# zero_board.net
KiCad netlist of a schematic drawn in EAGLE
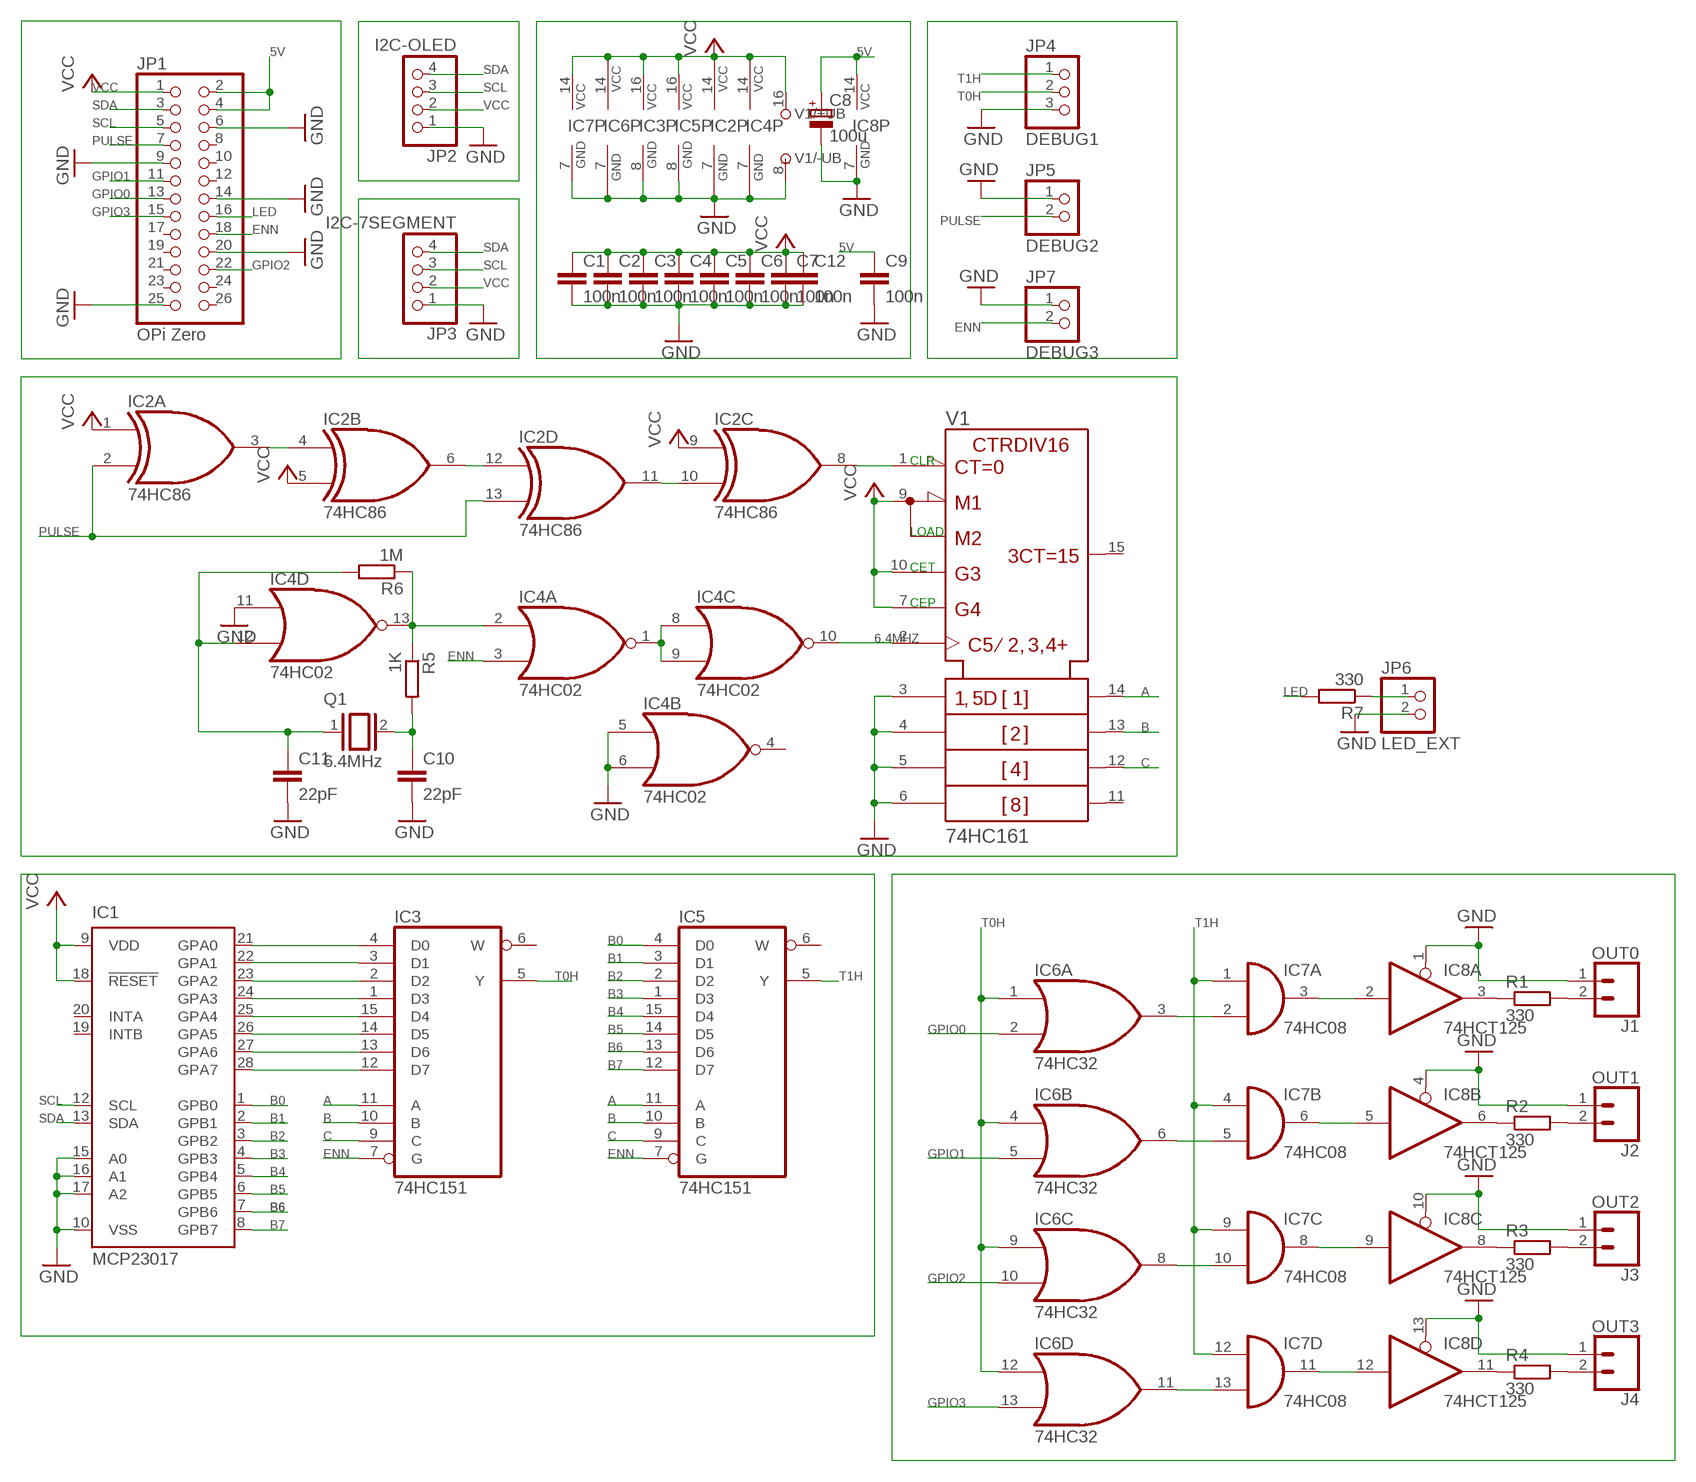
[diagram p0: schematic, sheet 1]

(export (version "E")
  (design (tool "Eeschema 10.0.6"))
  (components
    (comp (ref "C1")
      (value "100n")
      (footprint "eagle-import:C050-024X044")
      (libsource (lib "eagle-import") (part "C-EU050-024X044"))
    )
    (comp (ref "C2")
      (value "100n")
      (footprint "eagle-import:C050-024X044")
      (libsource (lib "eagle-import") (part "C-EU050-024X044"))
    )
    (comp (ref "C3")
      (value "100n")
      (footprint "eagle-import:C050-024X044")
      (libsource (lib "eagle-import") (part "C-EU050-024X044"))
    )
    (comp (ref "C4")
      (value "100n")
      (footprint "eagle-import:C050-024X044")
      (libsource (lib "eagle-import") (part "C-EU050-024X044"))
    )
    (comp (ref "C5")
      (value "100n")
      (footprint "eagle-import:C050-024X044")
      (libsource (lib "eagle-import") (part "C-EU050-024X044"))
    )
    (comp (ref "C6")
      (value "100n")
      (footprint "eagle-import:C050-024X044")
      (libsource (lib "eagle-import") (part "C-EU050-024X044"))
    )
    (comp (ref "C7")
      (value "100n")
      (footprint "eagle-import:C050-024X044")
      (libsource (lib "eagle-import") (part "C-EU050-024X044"))
    )
    (comp (ref "C8")
      (value "100u")
      (footprint "eagle-import:E2,5-6")
      (libsource (lib "eagle-import") (part "CPOL-EUE2.5-6"))
    )
    (comp (ref "C9")
      (value "100n")
      (footprint "eagle-import:C050-024X044")
      (libsource (lib "eagle-import") (part "C-EU050-024X044"))
    )
    (comp (ref "C10")
      (value "22pF")
      (footprint "eagle-import:C050-024X044")
      (libsource (lib "eagle-import") (part "C-EU050-024X044"))
    )
    (comp (ref "C11")
      (value "22pF")
      (footprint "eagle-import:C050-024X044")
      (libsource (lib "eagle-import") (part "C-EU050-024X044"))
    )
    (comp (ref "C12")
      (value "100n")
      (footprint "eagle-import:C050-024X044")
      (libsource (lib "eagle-import") (part "C-EU050-024X044"))
    )
    (comp (ref "IC1")
      (value "MCP23017")
      (footprint "eagle-import:DIL28-3")
      (fields (field (name "MF") "MICROCHIP") (field (name "MPN") "MCP23017-E/SP"))
      (libsource (lib "eagle-import") (part "MCP23017SP"))
    )
    (comp (ref "IC2")
      (value "74HC86")
      (footprint "eagle-import:DIL14")
      (libsource (lib "eagle-import") (part "7486NLS"))
    )
    (comp (ref "IC3")
      (value "74HC151")
      (footprint "eagle-import:DIL16")
      (libsource (lib "eagle-import") (part "74151NHC"))
    )
    (comp (ref "IC4")
      (value "74HC02")
      (footprint "eagle-import:DIL14")
      (libsource (lib "eagle-import") (part "7402N"))
    )
    (comp (ref "IC5")
      (value "74HC151")
      (footprint "eagle-import:DIL16")
      (libsource (lib "eagle-import") (part "74151NHC"))
    )
    (comp (ref "IC6")
      (value "74HC32")
      (footprint "eagle-import:DIL14")
      (libsource (lib "eagle-import") (part "7432NLS"))
    )
    (comp (ref "IC7")
      (value "74HC08")
      (footprint "eagle-import:DIL14")
      (libsource (lib "eagle-import") (part "7408NAS"))
    )
    (comp (ref "IC8")
      (value "74HCT125")
      (footprint "eagle-import:DIL14")
      (libsource (lib "eagle-import") (part "74125NHC"))
    )
    (comp (ref "J1")
      (value "OUT0")
      (footprint "eagle-import:SCREWTERMINAL-3.5MM-2")
      (libsource (lib "eagle-import") (part "CONN_023.5MM"))
    )
    (comp (ref "J2")
      (value "OUT1")
      (footprint "eagle-import:SCREWTERMINAL-3.5MM-2")
      (libsource (lib "eagle-import") (part "CONN_023.5MM"))
    )
    (comp (ref "J3")
      (value "OUT2")
      (footprint "eagle-import:SCREWTERMINAL-3.5MM-2")
      (libsource (lib "eagle-import") (part "CONN_023.5MM"))
    )
    (comp (ref "J4")
      (value "OUT3")
      (footprint "eagle-import:SCREWTERMINAL-3.5MM-2")
      (libsource (lib "eagle-import") (part "CONN_023.5MM"))
    )
    (comp (ref "JP1")
      (value "OPi Zero")
      (footprint "eagle-import:2X13")
      (libsource (lib "eagle-import") (part "PINHD-2X13"))
    )
    (comp (ref "JP2")
      (value "I2C-OLED")
      (footprint "eagle-import:1X04")
      (libsource (lib "eagle-import") (part "PINHD-1X4"))
    )
    (comp (ref "JP3")
      (value "I2C-7SEGMENT")
      (footprint "eagle-import:1X04")
      (libsource (lib "eagle-import") (part "PINHD-1X4"))
    )
    (comp (ref "JP4")
      (value "DEBUG1")
      (footprint "eagle-import:1X03_90")
      (libsource (lib "eagle-import") (part "PINHD-1X3/90"))
    )
    (comp (ref "JP5")
      (value "DEBUG2")
      (footprint "eagle-import:1X02_90")
      (libsource (lib "eagle-import") (part "PINHD-1X2/90"))
    )
    (comp (ref "JP6")
      (value "LED_EXT")
      (footprint "eagle-import:1X02_90")
      (libsource (lib "eagle-import") (part "PINHD-1X2/90"))
    )
    (comp (ref "JP7")
      (value "DEBUG3")
      (footprint "eagle-import:1X02_90")
      (libsource (lib "eagle-import") (part "PINHD-1X2/90"))
    )
    (comp (ref "Q1")
      (value "6.4MHz")
      (footprint "eagle-import:QS")
      (libsource (lib "eagle-import") (part "XTAL/S"))
    )
    (comp (ref "R1")
      (value "330")
      (footprint "eagle-import:0204_5")
      (libsource (lib "eagle-import") (part "R-EU_0204/5"))
    )
    (comp (ref "R2")
      (value "330")
      (footprint "eagle-import:0204_5")
      (libsource (lib "eagle-import") (part "R-EU_0204/5"))
    )
    (comp (ref "R3")
      (value "330")
      (footprint "eagle-import:0204_5")
      (libsource (lib "eagle-import") (part "R-EU_0204/5"))
    )
    (comp (ref "R4")
      (value "330")
      (footprint "eagle-import:0204_5")
      (libsource (lib "eagle-import") (part "R-EU_0204/5"))
    )
    (comp (ref "R5")
      (value "1K")
      (footprint "eagle-import:0204V")
      (libsource (lib "eagle-import") (part "R-EU_0204/2V"))
    )
    (comp (ref "R6")
      (value "1M")
      (footprint "eagle-import:0204V")
      (libsource (lib "eagle-import") (part "R-EU_0204/2V"))
    )
    (comp (ref "R7")
      (value "330")
      (footprint "eagle-import:0204V")
      (libsource (lib "eagle-import") (part "R-EU_0204/2V"))
    )
    (comp (ref "V1")
      (value "74HC161")
      (footprint "eagle-import:DIL16")
      (libsource (lib "eagle-import") (part "74161N"))
    )
  )
  (nets
    (net (code "1") (name "/5V") (class "Default")
      (node (ref "C8") (pin "+") (pinfunction "+_+") (pintype "passive"))
      (node (ref "C9") (pin "1") (pinfunction "1_1") (pintype "passive"))
      (node (ref "IC8") (pin "14") (pinfunction "VCC_14") (pintype "power_in"))
      (node (ref "JP1") (pin "2") (pinfunction "2_2") (pintype "passive"))
      (node (ref "JP1") (pin "4") (pinfunction "4_4") (pintype "passive"))
    )
    (net (code "2") (name "/6.4MHZ") (class "Default")
      (node (ref "IC4") (pin "10") (pinfunction "O_10") (pintype "output"))
      (node (ref "V1") (pin "2") (pinfunction "CLK_2") (pintype "input"))
    )
    (net (code "3") (name "/A") (class "Default")
      (node (ref "IC3") (pin "11") (pinfunction "A_11") (pintype "input"))
      (node (ref "IC5") (pin "11") (pinfunction "A_11") (pintype "input"))
      (node (ref "V1") (pin "14") (pinfunction "QA_14") (pintype "output"))
    )
    (net (code "4") (name "/B") (class "Default")
      (node (ref "IC3") (pin "10") (pinfunction "B_10") (pintype "input"))
      (node (ref "IC5") (pin "10") (pinfunction "B_10") (pintype "input"))
      (node (ref "V1") (pin "13") (pinfunction "QB_13") (pintype "output"))
    )
    (net (code "5") (name "/B0") (class "Default")
      (node (ref "IC1") (pin "1") (pinfunction "GPB0_1") (pintype "bidirectional"))
      (node (ref "IC5") (pin "4") (pinfunction "D0_4") (pintype "input"))
    )
    (net (code "6") (name "/B1") (class "Default")
      (node (ref "IC1") (pin "2") (pinfunction "GPB1_2") (pintype "bidirectional"))
      (node (ref "IC5") (pin "3") (pinfunction "D1_3") (pintype "input"))
    )
    (net (code "7") (name "/B2") (class "Default")
      (node (ref "IC1") (pin "3") (pinfunction "GPB2_3") (pintype "bidirectional"))
      (node (ref "IC5") (pin "2") (pinfunction "D2_2") (pintype "input"))
    )
    (net (code "8") (name "/B3") (class "Default")
      (node (ref "IC1") (pin "4") (pinfunction "GPB3_4") (pintype "bidirectional"))
      (node (ref "IC5") (pin "1") (pinfunction "D3_1") (pintype "input"))
    )
    (net (code "9") (name "/B4") (class "Default")
      (node (ref "IC1") (pin "5") (pinfunction "GPB4_5") (pintype "bidirectional"))
      (node (ref "IC5") (pin "15") (pinfunction "D4_15") (pintype "input"))
    )
    (net (code "10") (name "/B5") (class "Default")
      (node (ref "IC1") (pin "6") (pinfunction "GPB5_6") (pintype "bidirectional"))
      (node (ref "IC5") (pin "14") (pinfunction "D5_14") (pintype "input"))
    )
    (net (code "11") (name "/B6") (class "Default")
      (node (ref "IC1") (pin "7") (pinfunction "GPB6_7") (pintype "bidirectional"))
      (node (ref "IC5") (pin "13") (pinfunction "D6_13") (pintype "input"))
    )
    (net (code "12") (name "/B7") (class "Default")
      (node (ref "IC1") (pin "8") (pinfunction "GPB7_8") (pintype "bidirectional"))
      (node (ref "IC5") (pin "12") (pinfunction "D7_12") (pintype "input"))
    )
    (net (code "13") (name "/C") (class "Default")
      (node (ref "IC3") (pin "9") (pinfunction "C_9") (pintype "input"))
      (node (ref "IC5") (pin "9") (pinfunction "C_9") (pintype "input"))
      (node (ref "V1") (pin "12") (pinfunction "QC_12") (pintype "output"))
    )
    (net (code "14") (name "/ENN") (class "Default")
      (node (ref "IC3") (pin "7") (pinfunction "G_7") (pintype "input"))
      (node (ref "IC4") (pin "3") (pinfunction "I1_3") (pintype "input"))
      (node (ref "IC5") (pin "7") (pinfunction "G_7") (pintype "input"))
      (node (ref "JP1") (pin "18") (pinfunction "18_18") (pintype "passive"))
      (node (ref "JP7") (pin "2") (pinfunction "2_2") (pintype "passive"))
    )
    (net (code "15") (name "/GPIO0") (class "Default")
      (node (ref "IC6") (pin "2") (pinfunction "I1_2") (pintype "input"))
      (node (ref "JP1") (pin "13") (pinfunction "13_13") (pintype "passive"))
    )
    (net (code "16") (name "/GPIO1") (class "Default")
      (node (ref "IC6") (pin "5") (pinfunction "I1_5") (pintype "input"))
      (node (ref "JP1") (pin "11") (pinfunction "11_11") (pintype "passive"))
    )
    (net (code "17") (name "/GPIO2") (class "Default")
      (node (ref "IC6") (pin "10") (pinfunction "I1_10") (pintype "input"))
      (node (ref "JP1") (pin "22") (pinfunction "22_22") (pintype "passive"))
    )
    (net (code "18") (name "/GPIO3") (class "Default")
      (node (ref "IC6") (pin "13") (pinfunction "I1_13") (pintype "input"))
      (node (ref "JP1") (pin "15") (pinfunction "15_15") (pintype "passive"))
    )
    (net (code "19") (name "/LED") (class "Default")
      (node (ref "JP1") (pin "16") (pinfunction "16_16") (pintype "passive"))
      (node (ref "R7") (pin "2") (pinfunction "2_2") (pintype "passive"))
    )
    (net (code "20") (name "/PULSE") (class "Default")
      (node (ref "IC2") (pin "13") (pinfunction "I1_13") (pintype "input"))
      (node (ref "IC2") (pin "2") (pinfunction "I1_2") (pintype "input"))
      (node (ref "JP1") (pin "7") (pinfunction "7_7") (pintype "passive"))
      (node (ref "JP5") (pin "2") (pinfunction "2_2") (pintype "passive"))
    )
    (net (code "21") (name "/SCL") (class "Default")
      (node (ref "IC1") (pin "12") (pinfunction "SCL_12") (pintype "input"))
      (node (ref "JP1") (pin "5") (pinfunction "5_5") (pintype "passive"))
      (node (ref "JP2") (pin "3") (pinfunction "3_3") (pintype "passive"))
      (node (ref "JP3") (pin "3") (pinfunction "3_3") (pintype "passive"))
    )
    (net (code "22") (name "/SDA") (class "Default")
      (node (ref "IC1") (pin "13") (pinfunction "SDA_13") (pintype "bidirectional"))
      (node (ref "JP1") (pin "3") (pinfunction "3_3") (pintype "passive"))
      (node (ref "JP2") (pin "4") (pinfunction "4_4") (pintype "passive"))
      (node (ref "JP3") (pin "4") (pinfunction "4_4") (pintype "passive"))
    )
    (net (code "23") (name "/T0H") (class "Default")
      (node (ref "IC3") (pin "5") (pinfunction "Y_5") (pintype "output"))
      (node (ref "IC6") (pin "1") (pinfunction "I0_1") (pintype "input"))
      (node (ref "IC6") (pin "12") (pinfunction "I0_12") (pintype "input"))
      (node (ref "IC6") (pin "4") (pinfunction "I0_4") (pintype "input"))
      (node (ref "IC6") (pin "9") (pinfunction "I0_9") (pintype "input"))
      (node (ref "JP4") (pin "2") (pinfunction "2_2") (pintype "passive"))
    )
    (net (code "24") (name "/T1H") (class "Default")
      (node (ref "IC5") (pin "5") (pinfunction "Y_5") (pintype "output"))
      (node (ref "IC7") (pin "1") (pinfunction "I0_1") (pintype "input"))
      (node (ref "IC7") (pin "12") (pinfunction "I0_12") (pintype "input"))
      (node (ref "IC7") (pin "4") (pinfunction "I0_4") (pintype "input"))
      (node (ref "IC7") (pin "9") (pinfunction "I0_9") (pintype "input"))
      (node (ref "JP4") (pin "1") (pinfunction "1_1") (pintype "passive"))
    )
    (net (code "25") (name "GND") (class "Default")
      (node (ref "C1") (pin "2") (pinfunction "2_2") (pintype "passive"))
      (node (ref "C10") (pin "2") (pinfunction "2_2") (pintype "passive"))
      (node (ref "C11") (pin "2") (pinfunction "2_2") (pintype "passive"))
      (node (ref "C12") (pin "2") (pinfunction "2_2") (pintype "passive"))
      (node (ref "C2") (pin "2") (pinfunction "2_2") (pintype "passive"))
      (node (ref "C3") (pin "2") (pinfunction "2_2") (pintype "passive"))
      (node (ref "C4") (pin "2") (pinfunction "2_2") (pintype "passive"))
      (node (ref "C5") (pin "2") (pinfunction "2_2") (pintype "passive"))
      (node (ref "C6") (pin "2") (pinfunction "2_2") (pintype "passive"))
      (node (ref "C7") (pin "2") (pinfunction "2_2") (pintype "passive"))
      (node (ref "C8") (pin "-") (pinfunction "-_-") (pintype "passive"))
      (node (ref "C9") (pin "2") (pinfunction "2_2") (pintype "passive"))
      (node (ref "IC1") (pin "10") (pinfunction "VSS_10") (pintype "power_in"))
      (node (ref "IC1") (pin "15") (pinfunction "A0_15") (pintype "input"))
      (node (ref "IC1") (pin "16") (pinfunction "A1_16") (pintype "input"))
      (node (ref "IC1") (pin "17") (pinfunction "A2_17") (pintype "input"))
      (node (ref "IC2") (pin "7") (pinfunction "GND_7") (pintype "power_in"))
      (node (ref "IC3") (pin "8") (pinfunction "GND_8") (pintype "power_in"))
      (node (ref "IC4") (pin "11") (pinfunction "I0_11") (pintype "input"))
      (node (ref "IC4") (pin "5") (pinfunction "I0_5") (pintype "input"))
      (node (ref "IC4") (pin "6") (pinfunction "I1_6") (pintype "input"))
      (node (ref "IC4") (pin "7") (pinfunction "GND_7") (pintype "power_in"))
      (node (ref "IC5") (pin "8") (pinfunction "GND_8") (pintype "power_in"))
      (node (ref "IC6") (pin "7") (pinfunction "GND_7") (pintype "power_in"))
      (node (ref "IC7") (pin "7") (pinfunction "GND_7") (pintype "power_in"))
      (node (ref "IC8") (pin "1") (pinfunction "OE_1") (pintype "input"))
      (node (ref "IC8") (pin "10") (pinfunction "OE_10") (pintype "input"))
      (node (ref "IC8") (pin "13") (pinfunction "OE_13") (pintype "input"))
      (node (ref "IC8") (pin "4") (pinfunction "OE_4") (pintype "input"))
      (node (ref "IC8") (pin "7") (pinfunction "GND_7") (pintype "power_in"))
      (node (ref "J1") (pin "1") (pinfunction "1_1") (pintype "passive"))
      (node (ref "J2") (pin "1") (pinfunction "1_1") (pintype "passive"))
      (node (ref "J3") (pin "1") (pinfunction "1_1") (pintype "passive"))
      (node (ref "J4") (pin "1") (pinfunction "1_1") (pintype "passive"))
      (node (ref "JP1") (pin "14") (pinfunction "14_14") (pintype "passive"))
      (node (ref "JP1") (pin "20") (pinfunction "20_20") (pintype "passive"))
      (node (ref "JP1") (pin "25") (pinfunction "25_25") (pintype "passive"))
      (node (ref "JP1") (pin "6") (pinfunction "6_6") (pintype "passive"))
      (node (ref "JP1") (pin "9") (pinfunction "9_9") (pintype "passive"))
      (node (ref "JP2") (pin "1") (pinfunction "1_1") (pintype "passive"))
      (node (ref "JP3") (pin "1") (pinfunction "1_1") (pintype "passive"))
      (node (ref "JP4") (pin "3") (pinfunction "3_3") (pintype "passive"))
      (node (ref "JP5") (pin "1") (pinfunction "1_1") (pintype "passive"))
      (node (ref "JP6") (pin "2") (pinfunction "2_2") (pintype "passive"))
      (node (ref "JP7") (pin "1") (pinfunction "1_1") (pintype "passive"))
      (node (ref "V1") (pin "3") (pinfunction "A_3") (pintype "input"))
      (node (ref "V1") (pin "4") (pinfunction "B_4") (pintype "input"))
      (node (ref "V1") (pin "5") (pinfunction "C_5") (pintype "input"))
      (node (ref "V1") (pin "6") (pinfunction "D_6") (pintype "input"))
      (node (ref "V1") (pin "8") (pinfunction "-UB_8") (pintype "power_in"))
    )
    (net (code "26") (name "Net-(C10-Pad1)") (class "Default")
      (node (ref "C10") (pin "1") (pinfunction "1_1") (pintype "passive"))
      (node (ref "Q1") (pin "2") (pinfunction "2_2") (pintype "passive"))
      (node (ref "R5") (pin "2") (pinfunction "2_2") (pintype "passive"))
    )
    (net (code "27") (name "Net-(IC1-GPA0)") (class "Default")
      (node (ref "IC1") (pin "21") (pinfunction "GPA0_21") (pintype "bidirectional"))
      (node (ref "IC3") (pin "4") (pinfunction "D0_4") (pintype "input"))
    )
    (net (code "28") (name "Net-(IC1-GPA1)") (class "Default")
      (node (ref "IC1") (pin "22") (pinfunction "GPA1_22") (pintype "bidirectional"))
      (node (ref "IC3") (pin "3") (pinfunction "D1_3") (pintype "input"))
    )
    (net (code "29") (name "Net-(IC1-GPA2)") (class "Default")
      (node (ref "IC1") (pin "23") (pinfunction "GPA2_23") (pintype "bidirectional"))
      (node (ref "IC3") (pin "2") (pinfunction "D2_2") (pintype "input"))
    )
    (net (code "30") (name "Net-(IC1-GPA3)") (class "Default")
      (node (ref "IC1") (pin "24") (pinfunction "GPA3_24") (pintype "bidirectional"))
      (node (ref "IC3") (pin "1") (pinfunction "D3_1") (pintype "input"))
    )
    (net (code "31") (name "Net-(IC1-GPA4)") (class "Default")
      (node (ref "IC1") (pin "25") (pinfunction "GPA4_25") (pintype "bidirectional"))
      (node (ref "IC3") (pin "15") (pinfunction "D4_15") (pintype "input"))
    )
    (net (code "32") (name "Net-(IC1-GPA5)") (class "Default")
      (node (ref "IC1") (pin "26") (pinfunction "GPA5_26") (pintype "bidirectional"))
      (node (ref "IC3") (pin "14") (pinfunction "D5_14") (pintype "input"))
    )
    (net (code "33") (name "Net-(IC1-GPA6)") (class "Default")
      (node (ref "IC1") (pin "27") (pinfunction "GPA6_27") (pintype "bidirectional"))
      (node (ref "IC3") (pin "13") (pinfunction "D6_13") (pintype "input"))
    )
    (net (code "34") (name "Net-(IC1-GPA7)") (class "Default")
      (node (ref "IC1") (pin "28") (pinfunction "GPA7_28") (pintype "bidirectional"))
      (node (ref "IC3") (pin "12") (pinfunction "D7_12") (pintype "input"))
    )
    (net (code "35") (name "Net-(IC2A-O)") (class "Default")
      (node (ref "IC2") (pin "3") (pinfunction "O_3") (pintype "output"))
      (node (ref "IC2") (pin "4") (pinfunction "I0_4") (pintype "input"))
    )
    (net (code "36") (name "Net-(IC2B-O)") (class "Default")
      (node (ref "IC2") (pin "12") (pinfunction "I0_12") (pintype "input"))
      (node (ref "IC2") (pin "6") (pinfunction "O_6") (pintype "output"))
    )
    (net (code "37") (name "Net-(IC2C-I1)") (class "Default")
      (node (ref "IC2") (pin "10") (pinfunction "I1_10") (pintype "input"))
      (node (ref "IC2") (pin "11") (pinfunction "O_11") (pintype "output"))
    )
    (net (code "38") (name "Net-(IC2C-O)") (class "Default")
      (node (ref "IC2") (pin "8") (pinfunction "O_8") (pintype "output"))
      (node (ref "V1") (pin "1") (pinfunction "~{CLR}_1") (pintype "input"))
    )
    (net (code "39") (name "Net-(IC4A-I0)") (class "Default")
      (node (ref "IC4") (pin "13") (pinfunction "O_13") (pintype "output"))
      (node (ref "IC4") (pin "2") (pinfunction "I0_2") (pintype "input"))
      (node (ref "R5") (pin "1") (pinfunction "1_1") (pintype "passive"))
      (node (ref "R6") (pin "1") (pinfunction "1_1") (pintype "passive"))
    )
    (net (code "40") (name "Net-(IC4A-O)") (class "Default")
      (node (ref "IC4") (pin "1") (pinfunction "O_1") (pintype "output"))
      (node (ref "IC4") (pin "8") (pinfunction "I0_8") (pintype "input"))
      (node (ref "IC4") (pin "9") (pinfunction "I1_9") (pintype "input"))
    )
    (net (code "41") (name "Net-(IC4D-I1)") (class "Default")
      (node (ref "C11") (pin "1") (pinfunction "1_1") (pintype "passive"))
      (node (ref "IC4") (pin "12") (pinfunction "I1_12") (pintype "input"))
      (node (ref "Q1") (pin "1") (pinfunction "1_1") (pintype "passive"))
      (node (ref "R6") (pin "2") (pinfunction "2_2") (pintype "passive"))
    )
    (net (code "42") (name "Net-(IC6A-O)") (class "Default")
      (node (ref "IC6") (pin "3") (pinfunction "O_3") (pintype "output"))
      (node (ref "IC7") (pin "2") (pinfunction "I1_2") (pintype "input"))
    )
    (net (code "43") (name "Net-(IC6B-O)") (class "Default")
      (node (ref "IC6") (pin "6") (pinfunction "O_6") (pintype "output"))
      (node (ref "IC7") (pin "5") (pinfunction "I1_5") (pintype "input"))
    )
    (net (code "44") (name "Net-(IC6C-O)") (class "Default")
      (node (ref "IC6") (pin "8") (pinfunction "O_8") (pintype "output"))
      (node (ref "IC7") (pin "10") (pinfunction "I1_10") (pintype "input"))
    )
    (net (code "45") (name "Net-(IC6D-O)") (class "Default")
      (node (ref "IC6") (pin "11") (pinfunction "O_11") (pintype "output"))
      (node (ref "IC7") (pin "13") (pinfunction "I1_13") (pintype "input"))
    )
    (net (code "46") (name "Net-(IC7A-O)") (class "Default")
      (node (ref "IC7") (pin "3") (pinfunction "O_3") (pintype "output"))
      (node (ref "IC8") (pin "2") (pinfunction "I_2") (pintype "input"))
    )
    (net (code "47") (name "Net-(IC7B-O)") (class "Default")
      (node (ref "IC7") (pin "6") (pinfunction "O_6") (pintype "output"))
      (node (ref "IC8") (pin "5") (pinfunction "I_5") (pintype "input"))
    )
    (net (code "48") (name "Net-(IC7C-O)") (class "Default")
      (node (ref "IC7") (pin "8") (pinfunction "O_8") (pintype "output"))
      (node (ref "IC8") (pin "9") (pinfunction "I_9") (pintype "input"))
    )
    (net (code "49") (name "Net-(IC7D-O)") (class "Default")
      (node (ref "IC7") (pin "11") (pinfunction "O_11") (pintype "output"))
      (node (ref "IC8") (pin "12") (pinfunction "I_12") (pintype "input"))
    )
    (net (code "50") (name "Net-(IC8A-O)") (class "Default")
      (node (ref "IC8") (pin "3") (pinfunction "O_3") (pintype "tri_state"))
      (node (ref "R1") (pin "1") (pinfunction "1_1") (pintype "passive"))
    )
    (net (code "51") (name "Net-(IC8B-O)") (class "Default")
      (node (ref "IC8") (pin "6") (pinfunction "O_6") (pintype "tri_state"))
      (node (ref "R2") (pin "1") (pinfunction "1_1") (pintype "passive"))
    )
    (net (code "52") (name "Net-(IC8C-O)") (class "Default")
      (node (ref "IC8") (pin "8") (pinfunction "O_8") (pintype "tri_state"))
      (node (ref "R3") (pin "1") (pinfunction "1_1") (pintype "passive"))
    )
    (net (code "53") (name "Net-(IC8D-O)") (class "Default")
      (node (ref "IC8") (pin "11") (pinfunction "O_11") (pintype "tri_state"))
      (node (ref "R4") (pin "1") (pinfunction "1_1") (pintype "passive"))
    )
    (net (code "54") (name "Net-(J1-Pad2)") (class "Default")
      (node (ref "J1") (pin "2") (pinfunction "2_2") (pintype "passive"))
      (node (ref "R1") (pin "2") (pinfunction "2_2") (pintype "passive"))
    )
    (net (code "55") (name "Net-(J2-Pad2)") (class "Default")
      (node (ref "J2") (pin "2") (pinfunction "2_2") (pintype "passive"))
      (node (ref "R2") (pin "2") (pinfunction "2_2") (pintype "passive"))
    )
    (net (code "56") (name "Net-(J3-Pad2)") (class "Default")
      (node (ref "J3") (pin "2") (pinfunction "2_2") (pintype "passive"))
      (node (ref "R3") (pin "2") (pinfunction "2_2") (pintype "passive"))
    )
    (net (code "57") (name "Net-(J4-Pad2)") (class "Default")
      (node (ref "J4") (pin "2") (pinfunction "2_2") (pintype "passive"))
      (node (ref "R4") (pin "2") (pinfunction "2_2") (pintype "passive"))
    )
    (net (code "58") (name "Net-(JP6-Pad1)") (class "Default")
      (node (ref "JP6") (pin "1") (pinfunction "1_1") (pintype "passive"))
      (node (ref "R7") (pin "1") (pinfunction "1_1") (pintype "passive"))
    )
    (net (code "59") (name "VCC") (class "Default")
      (node (ref "C1") (pin "1") (pinfunction "1_1") (pintype "passive"))
      (node (ref "C12") (pin "1") (pinfunction "1_1") (pintype "passive"))
      (node (ref "C2") (pin "1") (pinfunction "1_1") (pintype "passive"))
      (node (ref "C3") (pin "1") (pinfunction "1_1") (pintype "passive"))
      (node (ref "C4") (pin "1") (pinfunction "1_1") (pintype "passive"))
      (node (ref "C5") (pin "1") (pinfunction "1_1") (pintype "passive"))
      (node (ref "C6") (pin "1") (pinfunction "1_1") (pintype "passive"))
      (node (ref "C7") (pin "1") (pinfunction "1_1") (pintype "passive"))
      (node (ref "IC1") (pin "18") (pinfunction "~{RESET}_18") (pintype "input"))
      (node (ref "IC1") (pin "9") (pinfunction "VDD_9") (pintype "power_in"))
      (node (ref "IC2") (pin "1") (pinfunction "I0_1") (pintype "input"))
      (node (ref "IC2") (pin "14") (pinfunction "VCC_14") (pintype "power_in"))
      (node (ref "IC2") (pin "5") (pinfunction "I1_5") (pintype "input"))
      (node (ref "IC2") (pin "9") (pinfunction "I0_9") (pintype "input"))
      (node (ref "IC3") (pin "16") (pinfunction "VCC_16") (pintype "power_in"))
      (node (ref "IC4") (pin "14") (pinfunction "VCC_14") (pintype "power_in"))
      (node (ref "IC5") (pin "16") (pinfunction "VCC_16") (pintype "power_in"))
      (node (ref "IC6") (pin "14") (pinfunction "VCC_14") (pintype "power_in"))
      (node (ref "IC7") (pin "14") (pinfunction "VCC_14") (pintype "power_in"))
      (node (ref "JP1") (pin "1") (pinfunction "1_1") (pintype "passive"))
      (node (ref "JP2") (pin "2") (pinfunction "2_2") (pintype "passive"))
      (node (ref "JP3") (pin "2") (pinfunction "2_2") (pintype "passive"))
      (node (ref "V1") (pin "10") (pinfunction "ENT_10") (pintype "input"))
      (node (ref "V1") (pin "16") (pinfunction "+UB_16") (pintype "power_in"))
      (node (ref "V1") (pin "7") (pinfunction "ENP_7") (pintype "input"))
      (node (ref "V1") (pin "9") (pinfunction "~{LOAD}_9") (pintype "input"))
    )
    (net (code "60") (name "unconnected-(IC1-INTA-Pad20)") (class "Default")
      (node (ref "IC1") (pin "20") (pinfunction "INTA_20") (pintype "output"))
    )
    (net (code "61") (name "unconnected-(IC1-INTB-Pad19)") (class "Default")
      (node (ref "IC1") (pin "19") (pinfunction "INTB_19") (pintype "output"))
    )
    (net (code "62") (name "unconnected-(IC3A-W-Pad6)") (class "Default")
      (node (ref "IC3") (pin "6") (pinfunction "W_6") (pintype "output"))
    )
    (net (code "63") (name "unconnected-(IC4B-O-Pad4)") (class "Default")
      (node (ref "IC4") (pin "4") (pinfunction "O_4") (pintype "output"))
    )
    (net (code "64") (name "unconnected-(IC5A-W-Pad6)") (class "Default")
      (node (ref "IC5") (pin "6") (pinfunction "W_6") (pintype "output"))
    )
    (net (code "65") (name "unconnected-(JP1-Pad8)") (class "Default")
      (node (ref "JP1") (pin "8") (pinfunction "8_8") (pintype "passive"))
    )
    (net (code "66") (name "unconnected-(JP1-Pad10)") (class "Default")
      (node (ref "JP1") (pin "10") (pinfunction "10_10") (pintype "passive"))
    )
    (net (code "67") (name "unconnected-(JP1-Pad12)") (class "Default")
      (node (ref "JP1") (pin "12") (pinfunction "12_12") (pintype "passive"))
    )
    (net (code "68") (name "unconnected-(JP1-Pad17)") (class "Default")
      (node (ref "JP1") (pin "17") (pinfunction "17_17") (pintype "passive"))
    )
    (net (code "69") (name "unconnected-(JP1-Pad19)") (class "Default")
      (node (ref "JP1") (pin "19") (pinfunction "19_19") (pintype "passive"))
    )
    (net (code "70") (name "unconnected-(JP1-Pad21)") (class "Default")
      (node (ref "JP1") (pin "21") (pinfunction "21_21") (pintype "passive"))
    )
    (net (code "71") (name "unconnected-(JP1-Pad23)") (class "Default")
      (node (ref "JP1") (pin "23") (pinfunction "23_23") (pintype "passive"))
    )
    (net (code "72") (name "unconnected-(JP1-Pad24)") (class "Default")
      (node (ref "JP1") (pin "24") (pinfunction "24_24") (pintype "passive"))
    )
    (net (code "73") (name "unconnected-(JP1-Pad26)") (class "Default")
      (node (ref "JP1") (pin "26") (pinfunction "26_26") (pintype "passive"))
    )
    (net (code "74") (name "unconnected-(V1C-QD-Pad11)") (class "Default")
      (node (ref "V1") (pin "11") (pinfunction "QD_11") (pintype "output"))
    )
    (net (code "75") (name "unconnected-(V1C-RCO-Pad15)") (class "Default")
      (node (ref "V1") (pin "15") (pinfunction "RCO_15") (pintype "output"))
    )
  )
)
